# st_linkv21_block1.net
KiCad netlist of a schematic drawn in Altium Designer
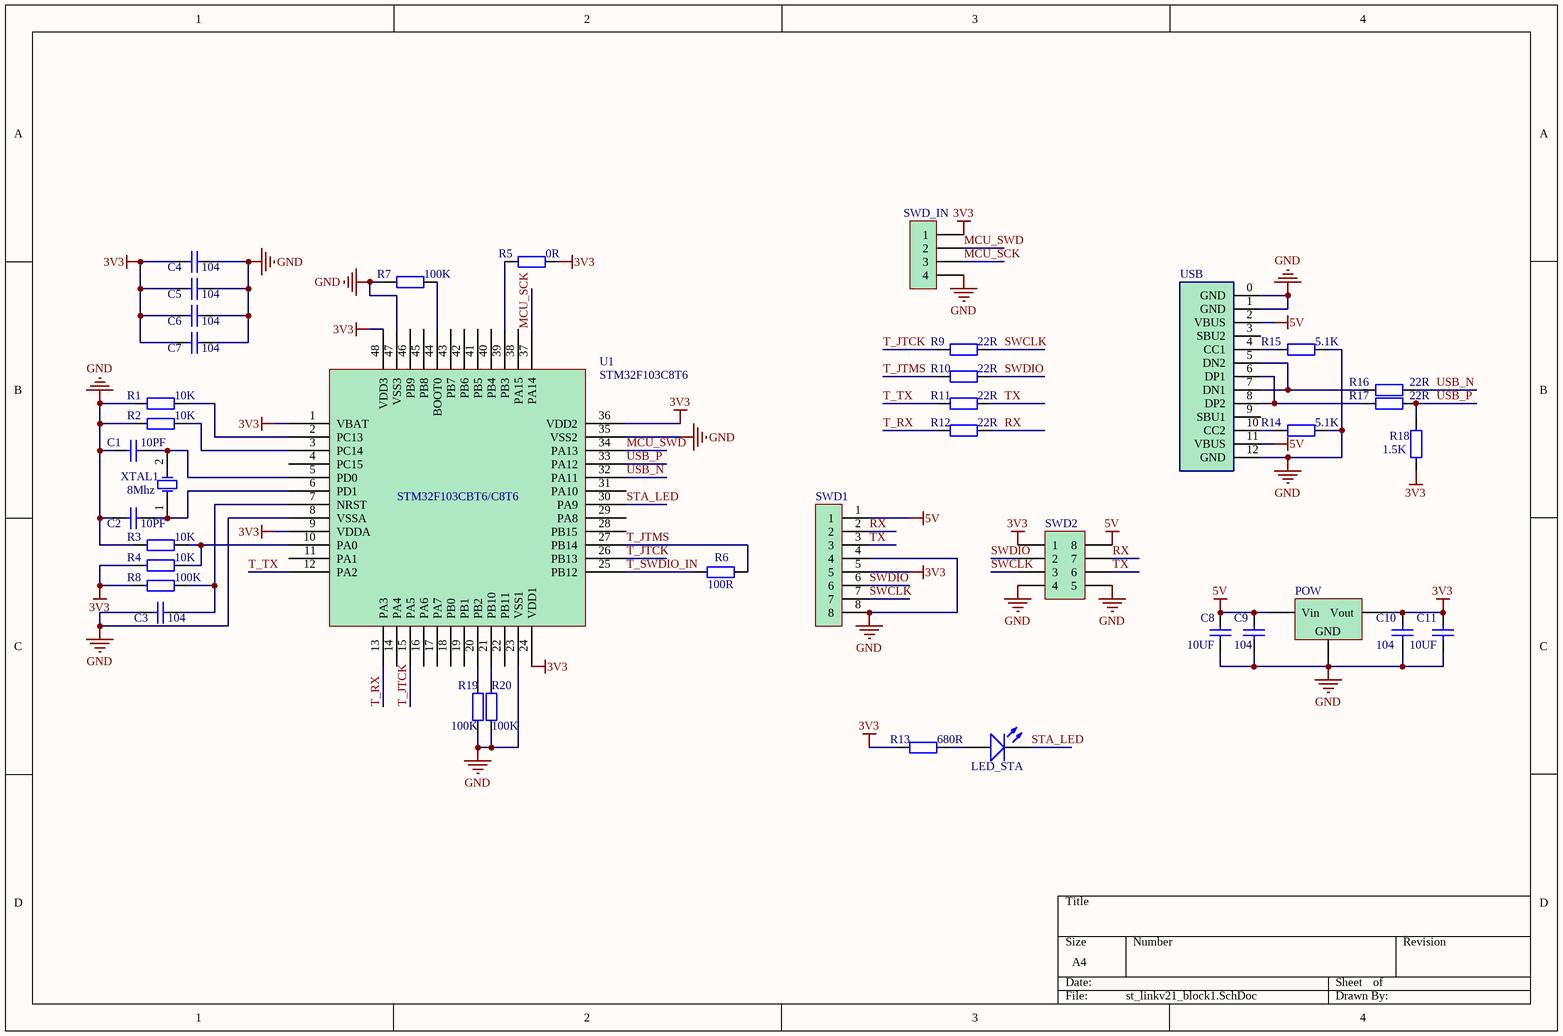
[diagram p0: st_linkv21_block1.SchDoc]

(export (version "E")
  (design (tool "Eeschema 10.0.6"))
  (components
    (comp (ref "C1") (value "10PF") (footprint "0603_C") (libsource (lib "MT_Device") (part "0603_CAP")))
    (comp (ref "C2") (value "10PF") (footprint "0603_C") (libsource (lib "MT_Device") (part "0603_CAP")))
    (comp (ref "C3") (value "104") (footprint "0603_C") (libsource (lib "MT_Device") (part "0603_CAP")))
    (comp (ref "C4") (value "104") (footprint "0603_C") (libsource (lib "MT_Device") (part "0603_CAP")))
    (comp (ref "C5") (value "104") (footprint "0603_C") (libsource (lib "MT_Device") (part "0603_CAP")))
    (comp (ref "C6") (value "104") (footprint "0603_C") (libsource (lib "MT_Device") (part "0603_CAP")))
    (comp (ref "C7") (value "104") (footprint "0603_C") (libsource (lib "MT_Device") (part "0603_CAP")))
    (comp (ref "C8") (value "10UF") (footprint "0603_C") (libsource (lib "MT_Device") (part "0603_CAP")))
    (comp (ref "C9") (value "104") (footprint "0603_C") (libsource (lib "MT_Device") (part "0603_CAP")))
    (comp (ref "C10") (value "104") (footprint "0603_C") (libsource (lib "MT_Device") (part "0603_CAP")))
    (comp (ref "C11") (value "10UF") (footprint "0603_C") (libsource (lib "MT_Device") (part "0603_CAP")))
    (comp (ref "LED_STA")
      (value "0805_LED")
      (footprint "0805_LED")
      (libsource (lib "MT_Device") (part "0805_LED"))
    )
    (comp (ref "POW")
      (value "AMS1117_3.3")
      (footprint "SOT223")
      (libsource (lib "MT_Device") (part "AMS1117_3.3"))
    )
    (comp (ref "R1") (value "10K") (footprint "0603_R") (libsource (lib "MT_Device") (part "0603_RES")))
    (comp (ref "R2") (value "10K") (footprint "0603_R") (libsource (lib "MT_Device") (part "0603_RES")))
    (comp (ref "R3") (value "10K") (footprint "0603_R") (libsource (lib "MT_Device") (part "0603_RES")))
    (comp (ref "R4") (value "10K") (footprint "0603_R") (libsource (lib "MT_Device") (part "0603_RES")))
    (comp (ref "R5") (value "0R") (footprint "0603_R") (libsource (lib "MT_Device") (part "0603_RES")))
    (comp (ref "R6") (value "100R") (footprint "0603_R") (libsource (lib "MT_Device") (part "0603_RES")))
    (comp (ref "R7") (value "100K") (footprint "0603_R") (libsource (lib "MT_Device") (part "0603_RES")))
    (comp (ref "R8") (value "100K") (footprint "0603_R") (libsource (lib "MT_Device") (part "0603_RES")))
    (comp (ref "R9") (value "22R") (footprint "0603_R") (libsource (lib "MT_Device") (part "0603_RES")))
    (comp (ref "R10") (value "22R") (footprint "0603_R") (libsource (lib "MT_Device") (part "0603_RES")))
    (comp (ref "R11") (value "22R") (footprint "0603_R") (libsource (lib "MT_Device") (part "0603_RES")))
    (comp (ref "R12") (value "22R") (footprint "0603_R") (libsource (lib "MT_Device") (part "0603_RES")))
    (comp (ref "R13") (value "680R") (footprint "0603_R") (libsource (lib "MT_Device") (part "0603_RES")))
    (comp (ref "R14") (value "5.1K") (footprint "0603_R") (libsource (lib "MT_Device") (part "0603_RES")))
    (comp (ref "R15") (value "5.1K") (footprint "0603_R") (libsource (lib "MT_Device") (part "0603_RES")))
    (comp (ref "R16") (value "22R") (footprint "0603_R") (libsource (lib "MT_Device") (part "0603_RES")))
    (comp (ref "R17") (value "22R") (footprint "0603_R") (libsource (lib "MT_Device") (part "0603_RES")))
    (comp (ref "R18") (value "1.5K") (footprint "0603_R") (libsource (lib "") (part "0603_RES_1")))
    (comp (ref "R19") (value "100K") (footprint "0603_R") (libsource (lib "") (part "0603_RES_1")))
    (comp (ref "R20") (value "100K") (footprint "0603_R") (libsource (lib "") (part "0603_RES_1")))
    (comp (ref "SWD1")
      (value "Header_1.27_8P")
      (footprint "HDR1.27_8P")
      (libsource (lib "MT_Connector") (part "Header_1.27_8P"))
    )
    (comp (ref "SWD2")
      (value "Header_2.54_4p_2")
      (footprint "HDR2_4P")
      (libsource (lib "MT_Connector") (part "Header_2.54_4p_2"))
    )
    (comp (ref "SWD_IN")
      (value "Header_2.54")
      (footprint "HDR1_4P")
      (libsource (lib "MT_Connector") (part "Header_2.54_4P"))
    )
    (comp (ref "U1")
      (value "STM32F103C8T6")
      (footprint "LQFP48")
      (libsource (lib "MT_Chip") (part "STM32F103C8T6"))
    )
    (comp (ref "USB")
      (value "USB_C_16P_SMT")
      (footprint "USB_C_16PIN_SMT")
      (libsource (lib "MT_Device") (part "USB_C_16P_SMT"))
    )
    (comp (ref "XTAL1")
      (value "8Mhz")
      (footprint "XTAL_5032_2")
      (libsource (lib "MT_Device") (part "XTAL_8MHz_5032_2"))
    )
  )
  (nets
    (net (code "1") (name "/MCU_SCK") (class "Default")
      (node (ref "SWD_IN") (pin "3") (pinfunction "3_3") (pintype "passive"))
      (node (ref "U1") (pin "37") (pinfunction "PA14_37") (pintype "passive"))
    )
    (net (code "2") (name "/MCU_SWD") (class "Default")
      (node (ref "SWD_IN") (pin "2") (pinfunction "2_2") (pintype "passive"))
      (node (ref "U1") (pin "34") (pinfunction "PA13_34") (pintype "passive"))
    )
    (net (code "3") (name "/RX") (class "Default")
      (node (ref "R12") (pin "2") (pinfunction "2_2") (pintype "passive"))
      (node (ref "SWD1") (pin "2") (pinfunction "2_2") (pintype "passive"))
      (node (ref "SWD2") (pin "7") (pinfunction "7_7") (pintype "passive"))
    )
    (net (code "4") (name "/STA_LED") (class "Default")
      (node (ref "LED_STA") (pin "K") (pinfunction "K_K") (pintype "passive"))
      (node (ref "U1") (pin "30") (pinfunction "PA9_30") (pintype "passive"))
    )
    (net (code "5") (name "/SWCLK") (class "Default")
      (node (ref "R9") (pin "2") (pinfunction "2_2") (pintype "passive"))
      (node (ref "SWD1") (pin "7") (pinfunction "7_7") (pintype "passive"))
      (node (ref "SWD2") (pin "3") (pinfunction "3_3") (pintype "passive"))
    )
    (net (code "6") (name "/SWDIO") (class "Default")
      (node (ref "R10") (pin "2") (pinfunction "2_2") (pintype "passive"))
      (node (ref "SWD1") (pin "6") (pinfunction "6_6") (pintype "passive"))
      (node (ref "SWD2") (pin "2") (pinfunction "2_2") (pintype "passive"))
    )
    (net (code "7") (name "/TX") (class "Default")
      (node (ref "R11") (pin "2") (pinfunction "2_2") (pintype "passive"))
      (node (ref "SWD1") (pin "3") (pinfunction "3_3") (pintype "passive"))
      (node (ref "SWD2") (pin "6") (pinfunction "6_6") (pintype "passive"))
    )
    (net (code "8") (name "/T_JTCK") (class "Default")
      (node (ref "R9") (pin "1") (pinfunction "1_1") (pintype "passive"))
      (node (ref "U1") (pin "15") (pinfunction "PA5_15") (pintype "passive"))
      (node (ref "U1") (pin "26") (pinfunction "PB13_26") (pintype "passive"))
    )
    (net (code "9") (name "/T_JTMS") (class "Default")
      (node (ref "R10") (pin "1") (pinfunction "1_1") (pintype "passive"))
      (node (ref "R6") (pin "2") (pinfunction "2_2") (pintype "passive"))
      (node (ref "U1") (pin "27") (pinfunction "PB14_27") (pintype "passive"))
    )
    (net (code "10") (name "/T_RX") (class "Default")
      (node (ref "R12") (pin "1") (pinfunction "1_1") (pintype "passive"))
      (node (ref "U1") (pin "13") (pinfunction "PA3_13") (pintype "passive"))
    )
    (net (code "11") (name "/T_SWDIO_IN") (class "Default")
      (node (ref "R6") (pin "1") (pinfunction "1_1") (pintype "passive"))
      (node (ref "U1") (pin "25") (pinfunction "PB12_25") (pintype "passive"))
    )
    (net (code "12") (name "/T_TX") (class "Default")
      (node (ref "R11") (pin "1") (pinfunction "1_1") (pintype "passive"))
      (node (ref "U1") (pin "12") (pinfunction "PA2_12") (pintype "passive"))
    )
    (net (code "13") (name "/USB_N") (class "Default")
      (node (ref "R16") (pin "2") (pinfunction "2_2") (pintype "passive"))
      (node (ref "U1") (pin "32") (pinfunction "PA11_32") (pintype "passive"))
    )
    (net (code "14") (name "/USB_P") (class "Default")
      (node (ref "R17") (pin "2") (pinfunction "2_2") (pintype "passive"))
      (node (ref "R18") (pin "2") (pinfunction "2_2") (pintype "passive"))
      (node (ref "U1") (pin "33") (pinfunction "PA12_33") (pintype "passive"))
    )
    (net (code "15") (name "3V3") (class "Default")
      (node (ref "C10") (pin "2") (pinfunction "2_2") (pintype "passive"))
      (node (ref "C11") (pin "2") (pinfunction "2_2") (pintype "passive"))
      (node (ref "C4") (pin "1") (pinfunction "1_1") (pintype "passive"))
      (node (ref "C5") (pin "1") (pinfunction "1_1") (pintype "passive"))
      (node (ref "C6") (pin "1") (pinfunction "1_1") (pintype "passive"))
      (node (ref "C7") (pin "1") (pinfunction "1_1") (pintype "passive"))
      (node (ref "POW") (pin "2") (pinfunction "Vout_2") (pintype "passive"))
      (node (ref "R13") (pin "1") (pinfunction "1_1") (pintype "passive"))
      (node (ref "R18") (pin "1") (pinfunction "1_1") (pintype "passive"))
      (node (ref "R4") (pin "1") (pinfunction "1_1") (pintype "passive"))
      (node (ref "R5") (pin "2") (pinfunction "2_2") (pintype "passive"))
      (node (ref "R8") (pin "1") (pinfunction "1_1") (pintype "passive"))
      (node (ref "SWD1") (pin "5") (pinfunction "5_5") (pintype "passive"))
      (node (ref "SWD2") (pin "1") (pinfunction "1_1") (pintype "passive"))
      (node (ref "SWD_IN") (pin "1") (pinfunction "1_1") (pintype "passive"))
      (node (ref "U1") (pin "1") (pinfunction "VBAT_1") (pintype "passive"))
      (node (ref "U1") (pin "24") (pinfunction "VDD1_24") (pintype "passive"))
      (node (ref "U1") (pin "36") (pinfunction "VDD2_36") (pintype "passive"))
      (node (ref "U1") (pin "48") (pinfunction "VDD3_48") (pintype "passive"))
      (node (ref "U1") (pin "9") (pinfunction "VDDA_9") (pintype "passive"))
    )
    (net (code "16") (name "5V") (class "Default")
      (node (ref "C8") (pin "2") (pinfunction "2_2") (pintype "passive"))
      (node (ref "C9") (pin "2") (pinfunction "2_2") (pintype "passive"))
      (node (ref "POW") (pin "3") (pinfunction "Vin_3") (pintype "passive"))
      (node (ref "SWD1") (pin "1") (pinfunction "1_1") (pintype "passive"))
      (node (ref "SWD2") (pin "8") (pinfunction "8_8") (pintype "passive"))
      (node (ref "USB") (pin "11") (pinfunction "VBUS_11") (pintype "passive"))
      (node (ref "USB") (pin "2") (pinfunction "VBUS_2") (pintype "passive"))
    )
    (net (code "17") (name "GND") (class "Default")
      (node (ref "C1") (pin "1") (pinfunction "1_1") (pintype "passive"))
      (node (ref "C10") (pin "1") (pinfunction "1_1") (pintype "passive"))
      (node (ref "C11") (pin "1") (pinfunction "1_1") (pintype "passive"))
      (node (ref "C2") (pin "1") (pinfunction "1_1") (pintype "passive"))
      (node (ref "C3") (pin "1") (pinfunction "1_1") (pintype "passive"))
      (node (ref "C4") (pin "2") (pinfunction "2_2") (pintype "passive"))
      (node (ref "C5") (pin "2") (pinfunction "2_2") (pintype "passive"))
      (node (ref "C6") (pin "2") (pinfunction "2_2") (pintype "passive"))
      (node (ref "C7") (pin "2") (pinfunction "2_2") (pintype "passive"))
      (node (ref "C8") (pin "1") (pinfunction "1_1") (pintype "passive"))
      (node (ref "C9") (pin "1") (pinfunction "1_1") (pintype "passive"))
      (node (ref "POW") (pin "1") (pinfunction "GND_1") (pintype "passive"))
      (node (ref "R1") (pin "1") (pinfunction "1_1") (pintype "passive"))
      (node (ref "R14") (pin "2") (pinfunction "2_2") (pintype "passive"))
      (node (ref "R15") (pin "2") (pinfunction "2_2") (pintype "passive"))
      (node (ref "R19") (pin "1") (pinfunction "1_1") (pintype "passive"))
      (node (ref "R2") (pin "1") (pinfunction "1_1") (pintype "passive"))
      (node (ref "R20") (pin "1") (pinfunction "1_1") (pintype "passive"))
      (node (ref "R3") (pin "1") (pinfunction "1_1") (pintype "passive"))
      (node (ref "R7") (pin "1") (pinfunction "1_1") (pintype "passive"))
      (node (ref "SWD1") (pin "4") (pinfunction "4_4") (pintype "passive"))
      (node (ref "SWD1") (pin "8") (pinfunction "8_8") (pintype "passive"))
      (node (ref "SWD2") (pin "4") (pinfunction "4_4") (pintype "passive"))
      (node (ref "SWD2") (pin "5") (pinfunction "5_5") (pintype "passive"))
      (node (ref "SWD_IN") (pin "4") (pinfunction "4_4") (pintype "passive"))
      (node (ref "U1") (pin "23") (pinfunction "VSS1_23") (pintype "passive"))
      (node (ref "U1") (pin "35") (pinfunction "VSS2_35") (pintype "passive"))
      (node (ref "U1") (pin "47") (pinfunction "VSS3_47") (pintype "passive"))
      (node (ref "U1") (pin "8") (pinfunction "VSSA_8") (pintype "passive"))
      (node (ref "USB") (pin "0") (pinfunction "GND_0") (pintype "passive"))
      (node (ref "USB") (pin "1") (pinfunction "GND_1") (pintype "passive"))
      (node (ref "USB") (pin "12") (pinfunction "GND_12") (pintype "passive"))
    )
    (net (code "18") (name "Net-(LED_STA-PadA)") (class "Default")
      (node (ref "LED_STA") (pin "A") (pinfunction "A_A") (pintype "passive"))
      (node (ref "R13") (pin "2") (pinfunction "2_2") (pintype "passive"))
    )
    (net (code "19") (name "Net-(U1-BOOT0)") (class "Default")
      (node (ref "R7") (pin "2") (pinfunction "2_2") (pintype "passive"))
      (node (ref "U1") (pin "44") (pinfunction "BOOT0_44") (pintype "passive"))
    )
    (net (code "20") (name "Net-(U1-NRST)") (class "Default")
      (node (ref "C3") (pin "2") (pinfunction "2_2") (pintype "passive"))
      (node (ref "R8") (pin "2") (pinfunction "2_2") (pintype "passive"))
      (node (ref "U1") (pin "7") (pinfunction "NRST_7") (pintype "passive"))
    )
    (net (code "21") (name "Net-(U1-PA0)") (class "Default")
      (node (ref "R3") (pin "2") (pinfunction "2_2") (pintype "passive"))
      (node (ref "R4") (pin "2") (pinfunction "2_2") (pintype "passive"))
      (node (ref "U1") (pin "10") (pinfunction "PA0_10") (pintype "passive"))
    )
    (net (code "22") (name "Net-(U1-PB2)") (class "Default")
      (node (ref "R19") (pin "2") (pinfunction "2_2") (pintype "passive"))
      (node (ref "U1") (pin "20") (pinfunction "PB2_20") (pintype "passive"))
    )
    (net (code "23") (name "Net-(U1-PB3)") (class "Default")
      (node (ref "R5") (pin "1") (pinfunction "1_1") (pintype "passive"))
      (node (ref "U1") (pin "39") (pinfunction "PB3_39") (pintype "passive"))
    )
    (net (code "24") (name "Net-(U1-PB10)") (class "Default")
      (node (ref "R20") (pin "2") (pinfunction "2_2") (pintype "passive"))
      (node (ref "U1") (pin "21") (pinfunction "PB10_21") (pintype "passive"))
    )
    (net (code "25") (name "Net-(U1-PC13)") (class "Default")
      (node (ref "R1") (pin "2") (pinfunction "2_2") (pintype "passive"))
      (node (ref "U1") (pin "2") (pinfunction "PC13_2") (pintype "passive"))
    )
    (net (code "26") (name "Net-(U1-PC14)") (class "Default")
      (node (ref "R2") (pin "2") (pinfunction "2_2") (pintype "passive"))
      (node (ref "U1") (pin "3") (pinfunction "PC14_3") (pintype "passive"))
    )
    (net (code "27") (name "Net-(U1-PD0)") (class "Default")
      (node (ref "C1") (pin "2") (pinfunction "2_2") (pintype "passive"))
      (node (ref "U1") (pin "5") (pinfunction "PD0_5") (pintype "passive"))
      (node (ref "XTAL1") (pin "2") (pinfunction "OSC2_2") (pintype "passive"))
    )
    (net (code "28") (name "Net-(U1-PD1)") (class "Default")
      (node (ref "C2") (pin "2") (pinfunction "2_2") (pintype "passive"))
      (node (ref "U1") (pin "6") (pinfunction "PD1_6") (pintype "passive"))
      (node (ref "XTAL1") (pin "1") (pinfunction "OSC1_1") (pintype "passive"))
    )
    (net (code "29") (name "Net-(USB-CC1)") (class "Default")
      (node (ref "R15") (pin "1") (pinfunction "1_1") (pintype "passive"))
      (node (ref "USB") (pin "4") (pinfunction "CC1_4") (pintype "passive"))
    )
    (net (code "30") (name "Net-(USB-CC2)") (class "Default")
      (node (ref "R14") (pin "1") (pinfunction "1_1") (pintype "passive"))
      (node (ref "USB") (pin "10") (pinfunction "CC2_10") (pintype "passive"))
    )
    (net (code "31") (name "Net-(USB-DN1)") (class "Default")
      (node (ref "R16") (pin "1") (pinfunction "1_1") (pintype "passive"))
      (node (ref "USB") (pin "5") (pinfunction "DN2_5") (pintype "passive"))
      (node (ref "USB") (pin "7") (pinfunction "DN1_7") (pintype "passive"))
    )
    (net (code "32") (name "Net-(USB-DP1)") (class "Default")
      (node (ref "R17") (pin "1") (pinfunction "1_1") (pintype "passive"))
      (node (ref "USB") (pin "6") (pinfunction "DP1_6") (pintype "passive"))
      (node (ref "USB") (pin "8") (pinfunction "DP2_8") (pintype "passive"))
    )
    (net (code "33") (name "unconnected-(U1-PA1-Pad11)") (class "Default")
      (node (ref "U1") (pin "11") (pinfunction "PA1_11") (pintype "passive"))
    )
    (net (code "34") (name "unconnected-(U1-PA4-Pad14)") (class "Default")
      (node (ref "U1") (pin "14") (pinfunction "PA4_14") (pintype "passive"))
    )
    (net (code "35") (name "unconnected-(U1-PA6-Pad16)") (class "Default")
      (node (ref "U1") (pin "16") (pinfunction "PA6_16") (pintype "passive"))
    )
    (net (code "36") (name "unconnected-(U1-PA7-Pad17)") (class "Default")
      (node (ref "U1") (pin "17") (pinfunction "PA7_17") (pintype "passive"))
    )
    (net (code "37") (name "unconnected-(U1-PA8-Pad29)") (class "Default")
      (node (ref "U1") (pin "29") (pinfunction "PA8_29") (pintype "passive"))
    )
    (net (code "38") (name "unconnected-(U1-PA10-Pad31)") (class "Default")
      (node (ref "U1") (pin "31") (pinfunction "PA10_31") (pintype "passive"))
    )
    (net (code "39") (name "unconnected-(U1-PA15-Pad38)") (class "Default")
      (node (ref "U1") (pin "38") (pinfunction "PA15_38") (pintype "passive"))
    )
    (net (code "40") (name "unconnected-(U1-PB0-Pad18)") (class "Default")
      (node (ref "U1") (pin "18") (pinfunction "PB0_18") (pintype "passive"))
    )
    (net (code "41") (name "unconnected-(U1-PB1-Pad19)") (class "Default")
      (node (ref "U1") (pin "19") (pinfunction "PB1_19") (pintype "passive"))
    )
    (net (code "42") (name "unconnected-(U1-PB4-Pad40)") (class "Default")
      (node (ref "U1") (pin "40") (pinfunction "PB4_40") (pintype "passive"))
    )
    (net (code "43") (name "unconnected-(U1-PB5-Pad41)") (class "Default")
      (node (ref "U1") (pin "41") (pinfunction "PB5_41") (pintype "passive"))
    )
    (net (code "44") (name "unconnected-(U1-PB6-Pad42)") (class "Default")
      (node (ref "U1") (pin "42") (pinfunction "PB6_42") (pintype "passive"))
    )
    (net (code "45") (name "unconnected-(U1-PB7-Pad43)") (class "Default")
      (node (ref "U1") (pin "43") (pinfunction "PB7_43") (pintype "passive"))
    )
    (net (code "46") (name "unconnected-(U1-PB8-Pad45)") (class "Default")
      (node (ref "U1") (pin "45") (pinfunction "PB8_45") (pintype "passive"))
    )
    (net (code "47") (name "unconnected-(U1-PB9-Pad46)") (class "Default")
      (node (ref "U1") (pin "46") (pinfunction "PB9_46") (pintype "passive"))
    )
    (net (code "48") (name "unconnected-(U1-PB11-Pad22)") (class "Default")
      (node (ref "U1") (pin "22") (pinfunction "PB11_22") (pintype "passive"))
    )
    (net (code "49") (name "unconnected-(U1-PB15-Pad28)") (class "Default")
      (node (ref "U1") (pin "28") (pinfunction "PB15_28") (pintype "passive"))
    )
    (net (code "50") (name "unconnected-(U1-PC15-Pad4)") (class "Default")
      (node (ref "U1") (pin "4") (pinfunction "PC15_4") (pintype "passive"))
    )
    (net (code "51") (name "unconnected-(USB-SBU1-Pad9)") (class "Default")
      (node (ref "USB") (pin "9") (pinfunction "SBU1_9") (pintype "passive"))
    )
    (net (code "52") (name "unconnected-(USB-SBU2-Pad3)") (class "Default")
      (node (ref "USB") (pin "3") (pinfunction "SBU2_3") (pintype "passive"))
    )
  )
)
